# Schem.net
KiCad netlist of a schematic drawn in Altium Designer
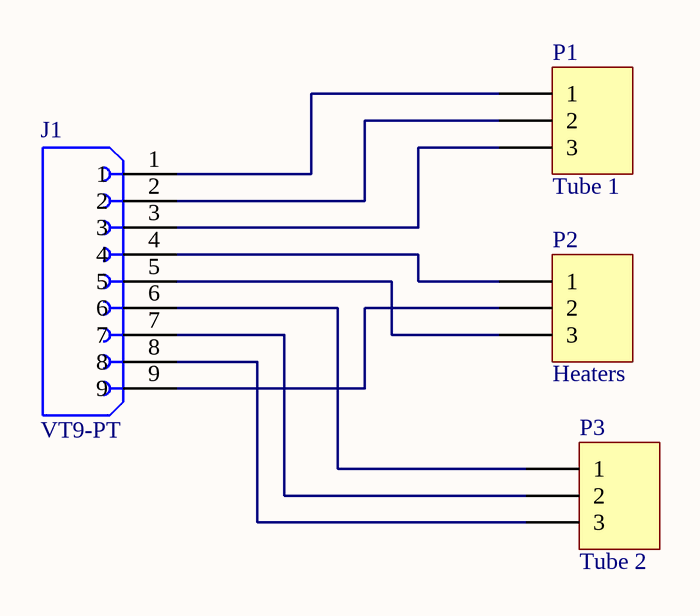
[diagram p0: Schem.SchDoc]

(export (version "E")
  (design (tool "Eeschema 10.0.6"))
  (components
    (comp (ref "J1")
      (value "VT9-PT")
      (footprint "BELTON_VT9-PT")
      (description "9 PIN MIN AUTOWAVE SOLDER SOCKET")
      (fields (field (name "MF") "Belton Engineering Co., Ltd."))
      (libsource (lib "VT9-PT") (part "VT9-PT"))
    )
    (comp (ref "P1")
      (value "Tube 1")
      (footprint "HDR1X3")
      (description "Header, 3-Pin")
      (fields (field (name "PUBLISHER") "Altium Limited"))
      (libsource (lib "Miscellaneous_Connectors") (part "Header 3"))
    )
    (comp (ref "P2")
      (value "Heaters")
      (footprint "HDR1X3")
      (description "Header, 3-Pin")
      (fields (field (name "PUBLISHER") "Altium Limited"))
      (libsource (lib "Miscellaneous_Connectors") (part "Header 3"))
    )
    (comp (ref "P3")
      (value "Tube 2")
      (footprint "HDR1X3")
      (description "Header, 3-Pin")
      (fields (field (name "PUBLISHER") "Altium Limited"))
      (libsource (lib "Miscellaneous_Connectors") (part "Header 3"))
    )
  )
  (nets
    (net (code "1") (name "Net-(J1-Pad1)") (class "Default")
      (node (ref "J1") (pin "1") (pinfunction "1_1") (pintype "passive"))
      (node (ref "P1") (pin "1") (pinfunction "1_1") (pintype "passive"))
    )
    (net (code "2") (name "Net-(J1-Pad2)") (class "Default")
      (node (ref "J1") (pin "2") (pinfunction "2_2") (pintype "passive"))
      (node (ref "P1") (pin "2") (pinfunction "2_2") (pintype "passive"))
    )
    (net (code "3") (name "Net-(J1-Pad3)") (class "Default")
      (node (ref "J1") (pin "3") (pinfunction "3_3") (pintype "passive"))
      (node (ref "P1") (pin "3") (pinfunction "3_3") (pintype "passive"))
    )
    (net (code "4") (name "Net-(J1-Pad4)") (class "Default")
      (node (ref "J1") (pin "4") (pinfunction "4_4") (pintype "passive"))
      (node (ref "P2") (pin "1") (pinfunction "1_1") (pintype "passive"))
    )
    (net (code "5") (name "Net-(J1-Pad5)") (class "Default")
      (node (ref "J1") (pin "5") (pinfunction "5_5") (pintype "passive"))
      (node (ref "P2") (pin "3") (pinfunction "3_3") (pintype "passive"))
    )
    (net (code "6") (name "Net-(J1-Pad6)") (class "Default")
      (node (ref "J1") (pin "6") (pinfunction "6_6") (pintype "passive"))
      (node (ref "P3") (pin "1") (pinfunction "1_1") (pintype "passive"))
    )
    (net (code "7") (name "Net-(J1-Pad7)") (class "Default")
      (node (ref "J1") (pin "7") (pinfunction "7_7") (pintype "passive"))
      (node (ref "P3") (pin "2") (pinfunction "2_2") (pintype "passive"))
    )
    (net (code "8") (name "Net-(J1-Pad8)") (class "Default")
      (node (ref "J1") (pin "8") (pinfunction "8_8") (pintype "passive"))
      (node (ref "P3") (pin "3") (pinfunction "3_3") (pintype "passive"))
    )
    (net (code "9") (name "Net-(J1-Pad9)") (class "Default")
      (node (ref "J1") (pin "9") (pinfunction "9_9") (pintype "passive"))
      (node (ref "P2") (pin "2") (pinfunction "2_2") (pintype "passive"))
    )
  )
)
